# board.net
KiCad netlist of a schematic drawn in EAGLE
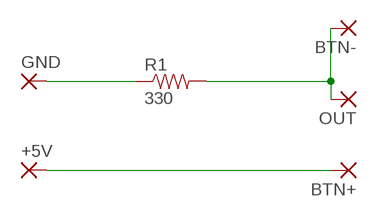
[diagram p0: schematic, sheet 1]

(export (version "E")
  (design (tool "Eeschema 10.0.6"))
  (components
    (comp (ref "+5V")
      (value "2,54/1,0")
      (footprint "eagle-import:2,54_1,0")
      (libsource (lib "eagle-import") (part "2,54/1,0"))
    )
    (comp (ref "BTN+")
      (value "2,54/1,0")
      (footprint "eagle-import:2,54_1,0")
      (libsource (lib "eagle-import") (part "2,54/1,0"))
    )
    (comp (ref "BTN-")
      (value "2,54/1,0")
      (footprint "eagle-import:2,54_1,0")
      (libsource (lib "eagle-import") (part "2,54/1,0"))
    )
    (comp (ref "GND")
      (value "2,54/1,0")
      (footprint "eagle-import:2,54_1,0")
      (libsource (lib "eagle-import") (part "2,54/1,0"))
    )
    (comp (ref "OUT")
      (value "2,54/1,0")
      (footprint "eagle-import:2,54_1,0")
      (libsource (lib "eagle-import") (part "2,54/1,0"))
    )
    (comp (ref "R1")
      (value "330")
      (footprint "eagle-import:AXIAL-0.4")
      (libsource (lib "eagle-import") (part "RESISTORPTH-1/4W"))
    )
  )
  (nets
    (net (code "1") (name "Net-(+5V-P)") (class "Default")
      (node (ref "+5V") (pin "1") (pinfunction "P_1") (pintype "passive"))
      (node (ref "BTN+") (pin "1") (pinfunction "P_1") (pintype "passive"))
    )
    (net (code "2") (name "Net-(BTN--P)") (class "Default")
      (node (ref "BTN-") (pin "1") (pinfunction "P_1") (pintype "passive"))
      (node (ref "OUT") (pin "1") (pinfunction "P_1") (pintype "passive"))
      (node (ref "R1") (pin "P$2") (pinfunction "2_P$2") (pintype "passive"))
    )
    (net (code "3") (name "Net-(GND-P)") (class "Default")
      (node (ref "GND") (pin "1") (pinfunction "P_1") (pintype "passive"))
      (node (ref "R1") (pin "P$1") (pinfunction "1_P$1") (pintype "passive"))
    )
  )
)
